# untitled.net
KiCad netlist of a schematic drawn in EAGLE
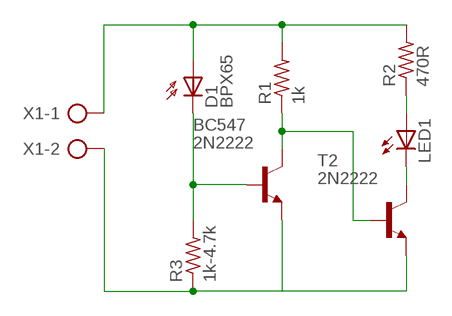
[diagram p0: schematic, sheet 1]

(export (version "E")
  (design (tool "Eeschema 10.0.6"))
  (components
    (comp (ref "BC547")
      (value "2N2222")
      (footprint "eagle-import:TO92-EBC-OVAL")
      (libsource (lib "eagle-import") (part "2N2222"))
    )
    (comp (ref "D1")
      (value "BPX65")
      (footprint "eagle-import:BPX65")
      (fields (field (name "MPN") "BPX65."))
      (libsource (lib "eagle-import") (part "BPX65"))
    )
    (comp (ref "LED1")
      (value "LED3MM")
      (footprint "eagle-import:LED3MM")
      (libsource (lib "eagle-import") (part "LED3MM"))
    )
    (comp (ref "R1")
      (value "1k")
      (footprint "eagle-import:0204_5")
      (libsource (lib "eagle-import") (part "R-US_0204/5"))
    )
    (comp (ref "R2")
      (value "470R")
      (footprint "eagle-import:0204_5")
      (libsource (lib "eagle-import") (part "R-US_0204/5"))
    )
    (comp (ref "R3")
      (value "1k-4.7k")
      (footprint "eagle-import:0204_5")
      (libsource (lib "eagle-import") (part "R-US_0204/5"))
    )
    (comp (ref "T2")
      (value "2N2222")
      (footprint "eagle-import:TO92-EBC-OVAL")
      (libsource (lib "eagle-import") (part "2N2222"))
    )
    (comp (ref "X1")
      (value "AK500/2")
      (footprint "eagle-import:AK500_2")
      (libsource (lib "eagle-import") (part "AK500/2"))
    )
  )
  (nets
    (net (code "1") (name "Net-(BC547-PadC)") (class "Default")
      (node (ref "BC547") (pin "C") (pinfunction "C_C") (pintype "passive"))
      (node (ref "R1") (pin "1") (pinfunction "1_1") (pintype "passive"))
      (node (ref "T2") (pin "B") (pinfunction "B_B") (pintype "passive"))
    )
    (net (code "2") (name "Net-(D1-C)") (class "Default")
      (node (ref "BC547") (pin "B") (pinfunction "B_B") (pintype "passive"))
      (node (ref "D1") (pin "K") (pinfunction "C_K") (pintype "passive"))
      (node (ref "R3") (pin "2") (pinfunction "2_2") (pintype "passive"))
    )
    (net (code "3") (name "Net-(LED1-C)") (class "Default")
      (node (ref "LED1") (pin "K") (pinfunction "C_K") (pintype "passive"))
      (node (ref "T2") (pin "C") (pinfunction "C_C") (pintype "passive"))
    )
    (net (code "4") (name "Net-(LED1-PadA)") (class "Default")
      (node (ref "LED1") (pin "A") (pinfunction "A_A") (pintype "passive"))
      (node (ref "R2") (pin "1") (pinfunction "1_1") (pintype "passive"))
    )
    (net (code "5") (name "Net-(X1A-KL)") (class "Default")
      (node (ref "D1") (pin "A") (pinfunction "A_A") (pintype "passive"))
      (node (ref "R1") (pin "2") (pinfunction "2_2") (pintype "passive"))
      (node (ref "R2") (pin "2") (pinfunction "2_2") (pintype "passive"))
      (node (ref "X1") (pin "1") (pinfunction "KL_1") (pintype "passive"))
    )
    (net (code "6") (name "Net-(X1B-KL)") (class "Default")
      (node (ref "BC547") (pin "E") (pinfunction "E_E") (pintype "passive"))
      (node (ref "R3") (pin "1") (pinfunction "1_1") (pintype "passive"))
      (node (ref "T2") (pin "E") (pinfunction "E_E") (pintype "passive"))
      (node (ref "X1") (pin "2") (pinfunction "KL_2") (pintype "passive"))
    )
  )
)
